# msp430fr5994-LQFP_80.net
KiCad netlist of a schematic drawn in EAGLE
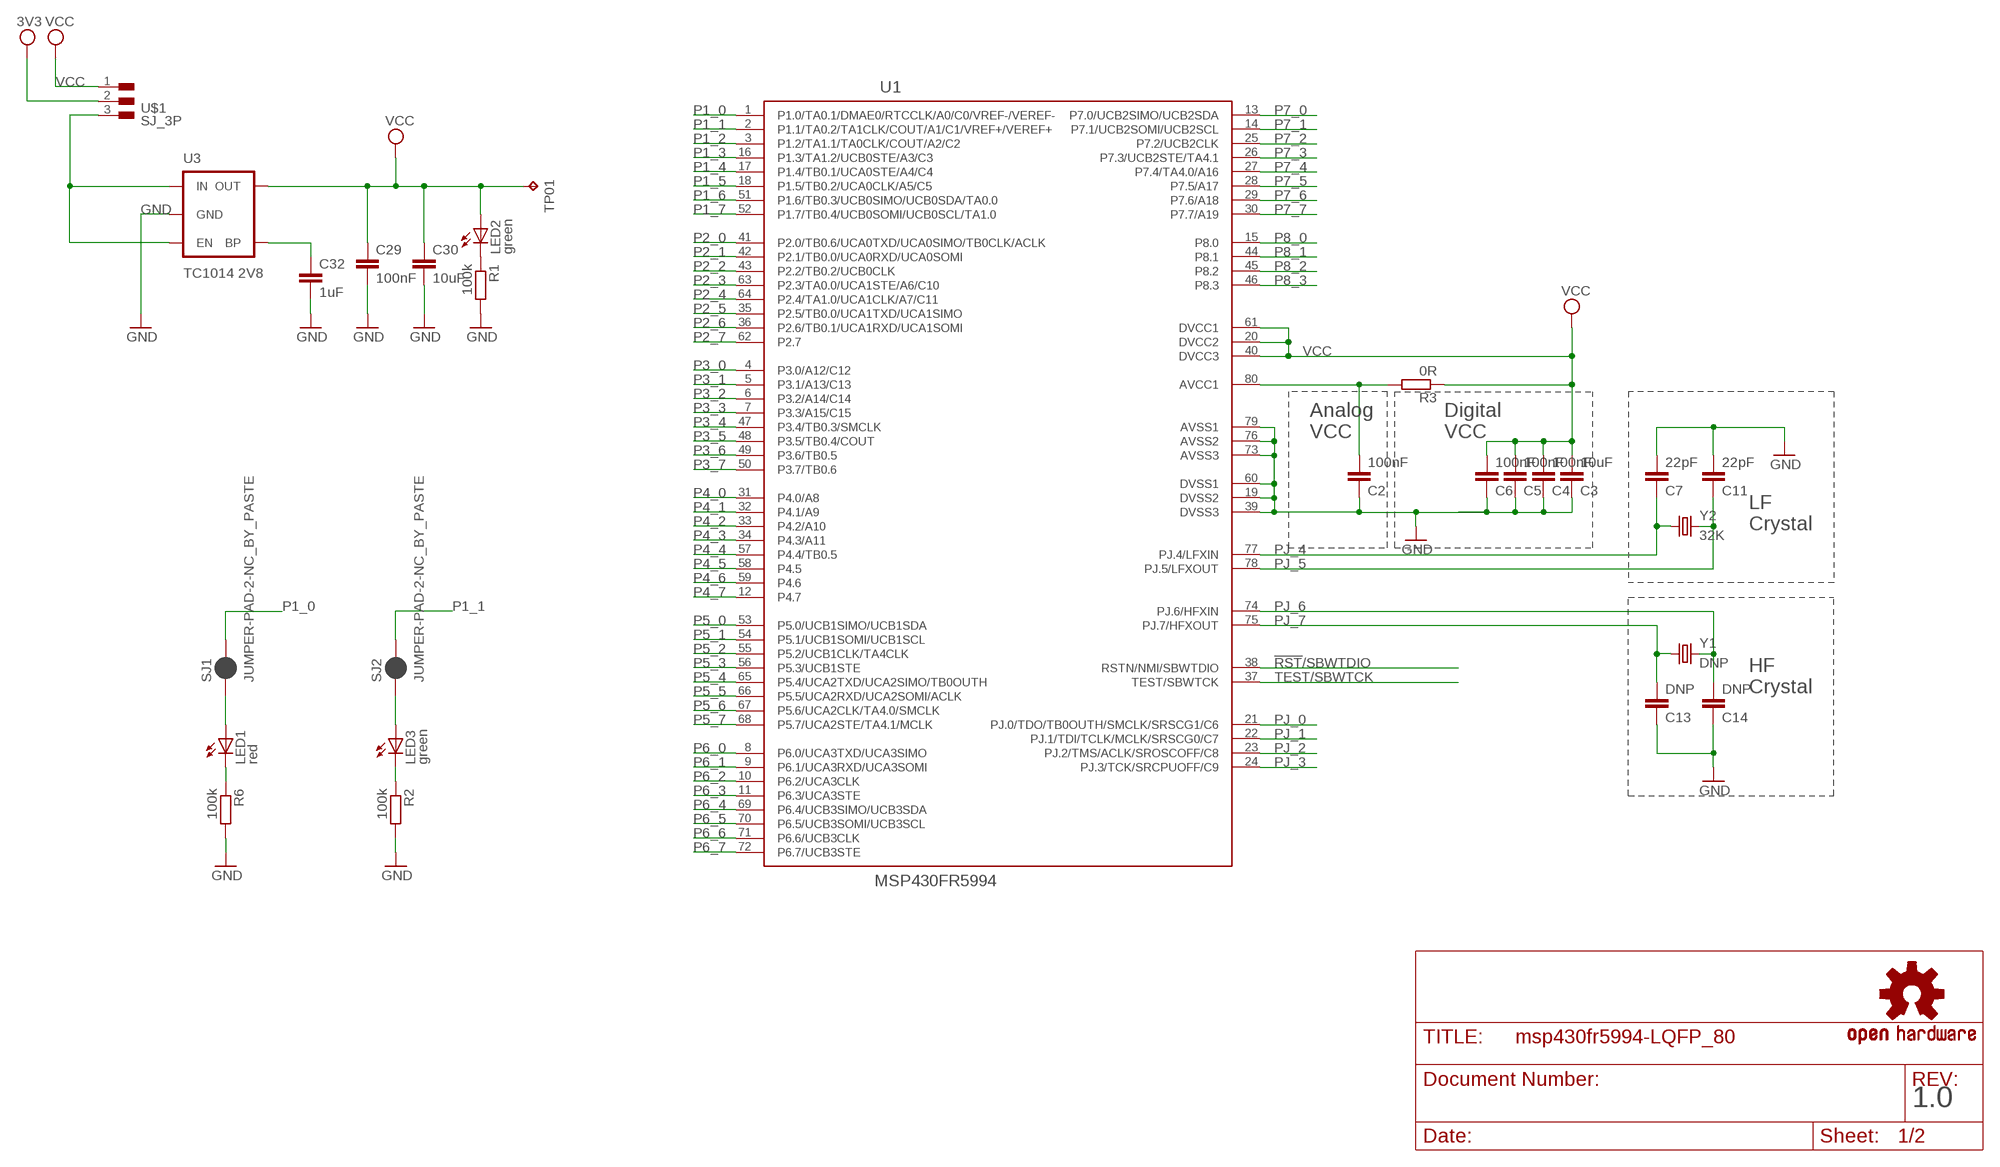
[diagram p0: schematic, sheet 1]
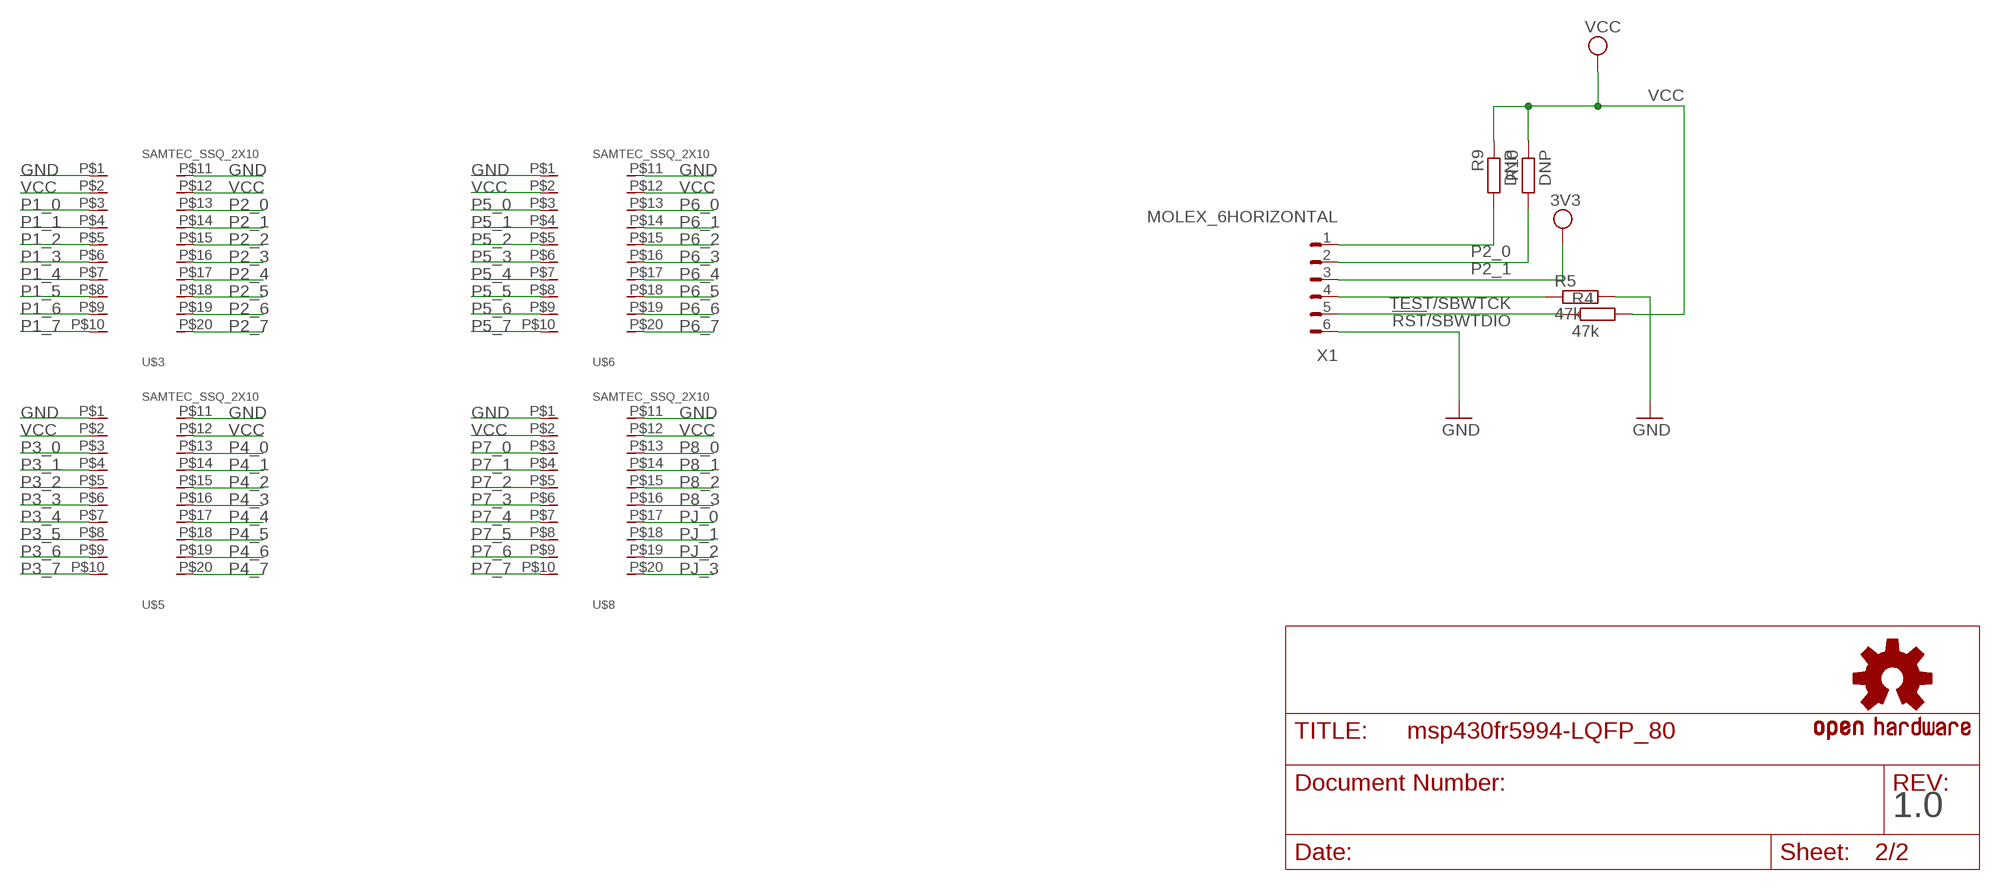
[diagram p1: schematic, sheet 2]

(export (version "E")
  (design (tool "Eeschema 10.0.6"))
  (components
    (comp (ref "R4")
      (value "47k")
      (footprint "eagle-import:R0805W")
      (libsource (lib "eagle-import") (part "R-EU_R0805W"))
    )
    (comp (ref "R5")
      (value "47k")
      (footprint "eagle-import:R0805W")
      (libsource (lib "eagle-import") (part "R-EU_R0805W"))
    )
    (comp (ref "R9")
      (value "DNP")
      (footprint "eagle-import:R0805W")
      (libsource (lib "eagle-import") (part "R-EU_R0805W"))
    )
    (comp (ref "R10")
      (value "DNP")
      (footprint "eagle-import:R0805W")
      (libsource (lib "eagle-import") (part "R-EU_R0805W"))
    )
    (comp (ref "U$2")
      (value "OSHW-LOGOM")
      (footprint "eagle-import:OSHW-LOGO-M")
      (libsource (lib "eagle-import") (part "OSHW-LOGOM"))
    )
    (comp (ref "U$3")
      (value "SAMTEC_SSQ_2X10")
      (footprint "eagle-import:SSQ-110-03-G-D")
      (libsource (lib "eagle-import") (part "SAMTEC_SSQ_2X10"))
    )
    (comp (ref "U$5")
      (value "SAMTEC_SSQ_2X10")
      (footprint "eagle-import:SSQ-110-03-G-D")
      (libsource (lib "eagle-import") (part "SAMTEC_SSQ_2X10"))
    )
    (comp (ref "U$6")
      (value "SAMTEC_SSQ_2X10")
      (footprint "eagle-import:SSQ-110-03-G-D")
      (libsource (lib "eagle-import") (part "SAMTEC_SSQ_2X10"))
    )
    (comp (ref "U$8")
      (value "SAMTEC_SSQ_2X10")
      (footprint "eagle-import:SSQ-110-03-G-D")
      (libsource (lib "eagle-import") (part "SAMTEC_SSQ_2X10"))
    )
    (comp (ref "X1")
      (value "MOLEX_6HORIZONTAL")
      (footprint "eagle-import:0530480610")
      (libsource (lib "eagle-import") (part "MOLEX_6HORIZONTAL"))
    )
    (comp (ref "C2")
      (value "100nF")
      (footprint "eagle-import:C0805")
      (libsource (lib "eagle-import") (part "C-EUC0805"))
    )
    (comp (ref "C3")
      (value "10uF")
      (footprint "eagle-import:C0805")
      (libsource (lib "eagle-import") (part "C-EUC0805"))
    )
    (comp (ref "C4")
      (value "100nF")
      (footprint "eagle-import:C0805")
      (libsource (lib "eagle-import") (part "C-EUC0805"))
    )
    (comp (ref "C5")
      (value "100nF")
      (footprint "eagle-import:C0805")
      (libsource (lib "eagle-import") (part "C-EUC0805"))
    )
    (comp (ref "C6")
      (value "100nF")
      (footprint "eagle-import:C0805")
      (libsource (lib "eagle-import") (part "C-EUC0805"))
    )
    (comp (ref "C7")
      (value "22pF")
      (footprint "eagle-import:C0805")
      (libsource (lib "eagle-import") (part "C-EUC0805"))
    )
    (comp (ref "C11")
      (value "22pF")
      (footprint "eagle-import:C0805")
      (libsource (lib "eagle-import") (part "C-EUC0805"))
    )
    (comp (ref "C13")
      (value "DNP")
      (footprint "eagle-import:C0805")
      (libsource (lib "eagle-import") (part "C-EUC0805"))
    )
    (comp (ref "C14")
      (value "DNP")
      (footprint "eagle-import:C0805")
      (libsource (lib "eagle-import") (part "C-EUC0805"))
    )
    (comp (ref "C29")
      (value "100nF")
      (footprint "eagle-import:C0805")
      (libsource (lib "eagle-import") (part "C-EUC0805"))
    )
    (comp (ref "C30")
      (value "10uF")
      (footprint "eagle-import:C1206")
      (libsource (lib "eagle-import") (part "C-EUC1206"))
    )
    (comp (ref "C32")
      (value "1uF")
      (footprint "eagle-import:C0805")
      (libsource (lib "eagle-import") (part "C-EUC0805"))
    )
    (comp (ref "LED1")
      (value "red")
      (footprint "eagle-import:CHIPLED_0805")
      (libsource (lib "eagle-import") (part "LEDCHIPLED_0805"))
    )
    (comp (ref "LED2")
      (value "green")
      (footprint "eagle-import:CHIPLED_0805")
      (libsource (lib "eagle-import") (part "LEDCHIPLED_0805"))
    )
    (comp (ref "LED3")
      (value "green")
      (footprint "eagle-import:CHIPLED_0805")
      (libsource (lib "eagle-import") (part "LEDCHIPLED_0805"))
    )
    (comp (ref "R1")
      (value "100k")
      (footprint "eagle-import:R0805W")
      (libsource (lib "eagle-import") (part "R-EU_R0805W"))
    )
    (comp (ref "R2")
      (value "100k")
      (footprint "eagle-import:R0805W")
      (libsource (lib "eagle-import") (part "R-EU_R0805W"))
    )
    (comp (ref "R3")
      (value "0R")
      (footprint "eagle-import:R0805W")
      (libsource (lib "eagle-import") (part "R-EU_R0805W"))
    )
    (comp (ref "R6")
      (value "100k")
      (footprint "eagle-import:R0805W")
      (libsource (lib "eagle-import") (part "R-EU_R0805W"))
    )
    (comp (ref "SJ1")
      (value "JUMPER-PAD-2-NC_BY_PASTE")
      (footprint "eagle-import:PAD-JUMPER-2-NC_BY_PASTE_YES_SILK")
      (libsource (lib "eagle-import") (part "JUMPER-PAD-2-NC_BY_PASTE"))
    )
    (comp (ref "SJ2")
      (value "JUMPER-PAD-2-NC_BY_PASTE")
      (footprint "eagle-import:PAD-JUMPER-2-NC_BY_PASTE_YES_SILK")
      (libsource (lib "eagle-import") (part "JUMPER-PAD-2-NC_BY_PASTE"))
    )
    (comp (ref "TP01")
      (value "TPTP12R")
      (footprint "eagle-import:TP12R")
      (libsource (lib "eagle-import") (part "TPTP12R"))
    )
    (comp (ref "U$1")
      (value "SJ_3P")
      (footprint "eagle-import:SJ_3P")
      (libsource (lib "eagle-import") (part "SJ_3P"))
    )
    (comp (ref "U$7")
      (value "OSHW-LOGOM")
      (footprint "eagle-import:OSHW-LOGO-M")
      (libsource (lib "eagle-import") (part "OSHW-LOGOM"))
    )
    (comp (ref "U1")
      (value "MSP430FR5994")
      (footprint "eagle-import:PN80")
      (libsource (lib "eagle-import") (part "MSP430FR5994"))
    )
    (comp (ref "U3")
      (value "TC1014 2V8")
      (footprint "eagle-import:SOT23-5")
      (libsource (lib "eagle-import") (part "V_REG_LDOSMD"))
    )
    (comp (ref "Y1")
      (value "DNP")
      (footprint "eagle-import:CRYSTAL-SMD-11.4X4.35")
      (libsource (lib "eagle-import") (part "CRYSTAL"))
    )
    (comp (ref "Y2")
      (value "32K")
      (footprint "eagle-import:CRYSTAL-SMD-3.2X1.5")
      (libsource (lib "eagle-import") (part "CRYSTAL3.2X1.5"))
    )
  )
  (nets
    (net (code "1") (name "3V3") (class "Default")
      (node (ref "U$1") (pin "2") (pinfunction "2_2") (pintype "passive"))
      (node (ref "X1") (pin "3") (pinfunction "4_3") (pintype "passive"))
    )
    (net (code "2") (name "GND") (class "Default")
      (node (ref "C11") (pin "2") (pinfunction "2_2") (pintype "passive"))
      (node (ref "C13") (pin "1") (pinfunction "1_1") (pintype "passive"))
      (node (ref "C14") (pin "1") (pinfunction "1_1") (pintype "passive"))
      (node (ref "C2") (pin "1") (pinfunction "1_1") (pintype "passive"))
      (node (ref "C29") (pin "2") (pinfunction "2_2") (pintype "passive"))
      (node (ref "C3") (pin "1") (pinfunction "1_1") (pintype "passive"))
      (node (ref "C30") (pin "2") (pinfunction "2_2") (pintype "passive"))
      (node (ref "C32") (pin "2") (pinfunction "2_2") (pintype "passive"))
      (node (ref "C4") (pin "1") (pinfunction "1_1") (pintype "passive"))
      (node (ref "C5") (pin "1") (pinfunction "1_1") (pintype "passive"))
      (node (ref "C6") (pin "1") (pinfunction "1_1") (pintype "passive"))
      (node (ref "C7") (pin "2") (pinfunction "2_2") (pintype "passive"))
      (node (ref "R1") (pin "2") (pinfunction "2_2") (pintype "passive"))
      (node (ref "R2") (pin "2") (pinfunction "2_2") (pintype "passive"))
      (node (ref "R5") (pin "2") (pinfunction "2_2") (pintype "passive"))
      (node (ref "R6") (pin "2") (pinfunction "2_2") (pintype "passive"))
      (node (ref "U$3") (pin "P$1") (pinfunction "P$1_P$1") (pintype "bidirectional"))
      (node (ref "U$3") (pin "P$11") (pinfunction "P$11_P$11") (pintype "bidirectional"))
      (node (ref "U$5") (pin "P$1") (pinfunction "P$1_P$1") (pintype "bidirectional"))
      (node (ref "U$5") (pin "P$11") (pinfunction "P$11_P$11") (pintype "bidirectional"))
      (node (ref "U$6") (pin "P$1") (pinfunction "P$1_P$1") (pintype "bidirectional"))
      (node (ref "U$6") (pin "P$11") (pinfunction "P$11_P$11") (pintype "bidirectional"))
      (node (ref "U$8") (pin "P$1") (pinfunction "P$1_P$1") (pintype "bidirectional"))
      (node (ref "U$8") (pin "P$11") (pinfunction "P$11_P$11") (pintype "bidirectional"))
      (node (ref "U1") (pin "19") (pinfunction "DVSS2_19") (pintype "power_in"))
      (node (ref "U1") (pin "39") (pinfunction "DVSS3_39") (pintype "power_in"))
      (node (ref "U1") (pin "60") (pinfunction "DVSS1_60") (pintype "power_in"))
      (node (ref "U1") (pin "73") (pinfunction "AVSS3_73") (pintype "power_in"))
      (node (ref "U1") (pin "76") (pinfunction "AVSS2_76") (pintype "power_in"))
      (node (ref "U1") (pin "79") (pinfunction "AVSS1_79") (pintype "power_in"))
      (node (ref "U3") (pin "2") (pinfunction "GND_2") (pintype "input"))
      (node (ref "X1") (pin "6") (pinfunction "1_6") (pintype "passive"))
    )
    (net (code "3") (name "Net-(LED1-PadA)") (class "Default")
      (node (ref "LED1") (pin "A") (pinfunction "A_A") (pintype "passive"))
      (node (ref "SJ1") (pin "1") (pinfunction "1_1") (pintype "passive"))
    )
    (net (code "4") (name "Net-(LED1-PadC)") (class "Default")
      (node (ref "LED1") (pin "C") (pinfunction "C_C") (pintype "passive"))
      (node (ref "R6") (pin "1") (pinfunction "1_1") (pintype "passive"))
    )
    (net (code "5") (name "Net-(LED2-PadC)") (class "Default")
      (node (ref "LED2") (pin "C") (pinfunction "C_C") (pintype "passive"))
      (node (ref "R1") (pin "1") (pinfunction "1_1") (pintype "passive"))
    )
    (net (code "6") (name "Net-(LED3-PadA)") (class "Default")
      (node (ref "LED3") (pin "A") (pinfunction "A_A") (pintype "passive"))
      (node (ref "SJ2") (pin "1") (pinfunction "1_1") (pintype "passive"))
    )
    (net (code "7") (name "Net-(LED3-PadC)") (class "Default")
      (node (ref "LED3") (pin "C") (pinfunction "C_C") (pintype "passive"))
      (node (ref "R2") (pin "1") (pinfunction "1_1") (pintype "passive"))
    )
    (net (code "8") (name "Net-(U1-AVCC1)") (class "Default")
      (node (ref "C2") (pin "2") (pinfunction "2_2") (pintype "passive"))
      (node (ref "R3") (pin "2") (pinfunction "2_2") (pintype "passive"))
      (node (ref "U1") (pin "80") (pinfunction "AVCC1_80") (pintype "power_in"))
    )
    (net (code "9") (name "Net-(U3-BP)") (class "Default")
      (node (ref "C32") (pin "1") (pinfunction "1_1") (pintype "passive"))
      (node (ref "U3") (pin "4") (pinfunction "BP_4") (pintype "input"))
    )
    (net (code "10") (name "Net-(U3-EN)") (class "Default")
      (node (ref "U$1") (pin "3") (pinfunction "3_3") (pintype "passive"))
      (node (ref "U3") (pin "1") (pinfunction "IN_1") (pintype "input"))
      (node (ref "U3") (pin "3") (pinfunction "EN_3") (pintype "input"))
    )
    (net (code "11") (name "P1_0") (class "Default")
      (node (ref "SJ1") (pin "2") (pinfunction "2_2") (pintype "passive"))
      (node (ref "U$3") (pin "P$3") (pinfunction "P$3_P$3") (pintype "bidirectional"))
      (node (ref "U1") (pin "1") (pinfunction "P1.0/TA0.1/DMAE0/RTCCLK/A0/C0/VREF-/VEREF-_1") (pintype "power_in"))
    )
    (net (code "12") (name "P1_1") (class "Default")
      (node (ref "SJ2") (pin "2") (pinfunction "2_2") (pintype "passive"))
      (node (ref "U$3") (pin "P$4") (pinfunction "P$4_P$4") (pintype "bidirectional"))
      (node (ref "U1") (pin "2") (pinfunction "P1.1/TA0.2/TA1CLK/COUT/A1/C1/VREF+/VEREF+_2") (pintype "power_in"))
    )
    (net (code "13") (name "P1_2") (class "Default")
      (node (ref "U$3") (pin "P$5") (pinfunction "P$5_P$5") (pintype "bidirectional"))
      (node (ref "U1") (pin "3") (pinfunction "P1.2/TA1.1/TA0CLK/COUT/A2/C2_3") (pintype "power_in"))
    )
    (net (code "14") (name "P1_3") (class "Default")
      (node (ref "U$3") (pin "P$6") (pinfunction "P$6_P$6") (pintype "bidirectional"))
      (node (ref "U1") (pin "16") (pinfunction "P1.3/TA1.2/UCB0STE/A3/C3_16") (pintype "power_in"))
    )
    (net (code "15") (name "P1_4") (class "Default")
      (node (ref "U$3") (pin "P$7") (pinfunction "P$7_P$7") (pintype "bidirectional"))
      (node (ref "U1") (pin "17") (pinfunction "P1.4/TB0.1/UCA0STE/A4/C4_17") (pintype "power_in"))
    )
    (net (code "16") (name "P1_5") (class "Default")
      (node (ref "U$3") (pin "P$8") (pinfunction "P$8_P$8") (pintype "bidirectional"))
      (node (ref "U1") (pin "18") (pinfunction "P1.5/TB0.2/UCA0CLK/A5/C5_18") (pintype "power_in"))
    )
    (net (code "17") (name "P1_6") (class "Default")
      (node (ref "U$3") (pin "P$9") (pinfunction "P$9_P$9") (pintype "bidirectional"))
      (node (ref "U1") (pin "51") (pinfunction "P1.6/TB0.3/UCB0SIMO/UCB0SDA/TA0.0_51") (pintype "power_in"))
    )
    (net (code "18") (name "P1_7") (class "Default")
      (node (ref "U$3") (pin "P$10") (pinfunction "P$10_P$10") (pintype "bidirectional"))
      (node (ref "U1") (pin "52") (pinfunction "P1.7/TB0.4/UCB0SOMI/UCB0SCL/TA1.0_52") (pintype "power_in"))
    )
    (net (code "19") (name "P2_0") (class "Default")
      (node (ref "R9") (pin "2") (pinfunction "2_2") (pintype "passive"))
      (node (ref "U$3") (pin "P$13") (pinfunction "P$13_P$13") (pintype "bidirectional"))
      (node (ref "U1") (pin "41") (pinfunction "P2.0/TB0.6/UCA0TXD/UCA0SIMO/TB0CLK/ACLK_41") (pintype "power_in"))
      (node (ref "X1") (pin "1") (pinfunction "6_1") (pintype "passive"))
    )
    (net (code "20") (name "P2_1") (class "Default")
      (node (ref "R10") (pin "2") (pinfunction "2_2") (pintype "passive"))
      (node (ref "U$3") (pin "P$14") (pinfunction "P$14_P$14") (pintype "bidirectional"))
      (node (ref "U1") (pin "42") (pinfunction "P2.1/TB0.0/UCA0RXD/UCA0SOMI_42") (pintype "power_in"))
      (node (ref "X1") (pin "2") (pinfunction "5_2") (pintype "passive"))
    )
    (net (code "21") (name "P2_2") (class "Default")
      (node (ref "U$3") (pin "P$15") (pinfunction "P$15_P$15") (pintype "bidirectional"))
      (node (ref "U1") (pin "43") (pinfunction "P2.2/TB0.2/UCB0CLK_43") (pintype "power_in"))
    )
    (net (code "22") (name "P2_3") (class "Default")
      (node (ref "U$3") (pin "P$16") (pinfunction "P$16_P$16") (pintype "bidirectional"))
      (node (ref "U1") (pin "63") (pinfunction "P2.3/TA0.0/UCA1STE/A6/C10_63") (pintype "power_in"))
    )
    (net (code "23") (name "P2_4") (class "Default")
      (node (ref "U$3") (pin "P$17") (pinfunction "P$17_P$17") (pintype "bidirectional"))
      (node (ref "U1") (pin "64") (pinfunction "P2.4/TA1.0/UCA1CLK/A7/C11_64") (pintype "power_in"))
    )
    (net (code "24") (name "P2_5") (class "Default")
      (node (ref "U$3") (pin "P$18") (pinfunction "P$18_P$18") (pintype "bidirectional"))
      (node (ref "U1") (pin "35") (pinfunction "P2.5/TB0.0/UCA1TXD/UCA1SIMO_35") (pintype "power_in"))
    )
    (net (code "25") (name "P2_6") (class "Default")
      (node (ref "U$3") (pin "P$19") (pinfunction "P$19_P$19") (pintype "bidirectional"))
      (node (ref "U1") (pin "36") (pinfunction "P2.6/TB0.1/UCA1RXD/UCA1SOMI_36") (pintype "power_in"))
    )
    (net (code "26") (name "P2_7") (class "Default")
      (node (ref "U$3") (pin "P$20") (pinfunction "P$20_P$20") (pintype "bidirectional"))
      (node (ref "U1") (pin "62") (pinfunction "P2.7_62") (pintype "power_in"))
    )
    (net (code "27") (name "P3_0") (class "Default")
      (node (ref "U$5") (pin "P$3") (pinfunction "P$3_P$3") (pintype "bidirectional"))
      (node (ref "U1") (pin "4") (pinfunction "P3.0/A12/C12_4") (pintype "power_in"))
    )
    (net (code "28") (name "P3_1") (class "Default")
      (node (ref "U$5") (pin "P$4") (pinfunction "P$4_P$4") (pintype "bidirectional"))
      (node (ref "U1") (pin "5") (pinfunction "P3.1/A13/C13_5") (pintype "power_in"))
    )
    (net (code "29") (name "P3_2") (class "Default")
      (node (ref "U$5") (pin "P$5") (pinfunction "P$5_P$5") (pintype "bidirectional"))
      (node (ref "U1") (pin "6") (pinfunction "P3.2/A14/C14_6") (pintype "power_in"))
    )
    (net (code "30") (name "P3_3") (class "Default")
      (node (ref "U$5") (pin "P$6") (pinfunction "P$6_P$6") (pintype "bidirectional"))
      (node (ref "U1") (pin "7") (pinfunction "P3.3/A15/C15_7") (pintype "power_in"))
    )
    (net (code "31") (name "P3_4") (class "Default")
      (node (ref "U$5") (pin "P$7") (pinfunction "P$7_P$7") (pintype "bidirectional"))
      (node (ref "U1") (pin "47") (pinfunction "P3.4/TB0.3/SMCLK_47") (pintype "power_in"))
    )
    (net (code "32") (name "P3_5") (class "Default")
      (node (ref "U$5") (pin "P$8") (pinfunction "P$8_P$8") (pintype "bidirectional"))
      (node (ref "U1") (pin "48") (pinfunction "P3.5/TB0.4/COUT_48") (pintype "power_in"))
    )
    (net (code "33") (name "P3_6") (class "Default")
      (node (ref "U$5") (pin "P$9") (pinfunction "P$9_P$9") (pintype "bidirectional"))
      (node (ref "U1") (pin "49") (pinfunction "P3.6/TB0.5_49") (pintype "power_in"))
    )
    (net (code "34") (name "P3_7") (class "Default")
      (node (ref "U$5") (pin "P$10") (pinfunction "P$10_P$10") (pintype "bidirectional"))
      (node (ref "U1") (pin "50") (pinfunction "P3.7/TB0.6_50") (pintype "power_in"))
    )
    (net (code "35") (name "P4_0") (class "Default")
      (node (ref "U$5") (pin "P$13") (pinfunction "P$13_P$13") (pintype "bidirectional"))
      (node (ref "U1") (pin "31") (pinfunction "P4.0/A8_31") (pintype "power_in"))
    )
    (net (code "36") (name "P4_1") (class "Default")
      (node (ref "U$5") (pin "P$14") (pinfunction "P$14_P$14") (pintype "bidirectional"))
      (node (ref "U1") (pin "32") (pinfunction "P4.1/A9_32") (pintype "power_in"))
    )
    (net (code "37") (name "P4_2") (class "Default")
      (node (ref "U$5") (pin "P$15") (pinfunction "P$15_P$15") (pintype "bidirectional"))
      (node (ref "U1") (pin "33") (pinfunction "P4.2/A10_33") (pintype "power_in"))
    )
    (net (code "38") (name "P4_3") (class "Default")
      (node (ref "U$5") (pin "P$16") (pinfunction "P$16_P$16") (pintype "bidirectional"))
      (node (ref "U1") (pin "34") (pinfunction "P4.3/A11_34") (pintype "power_in"))
    )
    (net (code "39") (name "P4_4") (class "Default")
      (node (ref "U$5") (pin "P$17") (pinfunction "P$17_P$17") (pintype "bidirectional"))
      (node (ref "U1") (pin "57") (pinfunction "P4.4/TB0.5_57") (pintype "power_in"))
    )
    (net (code "40") (name "P4_5") (class "Default")
      (node (ref "U$5") (pin "P$18") (pinfunction "P$18_P$18") (pintype "bidirectional"))
      (node (ref "U1") (pin "58") (pinfunction "P4.5_58") (pintype "power_in"))
    )
    (net (code "41") (name "P4_6") (class "Default")
      (node (ref "U$5") (pin "P$19") (pinfunction "P$19_P$19") (pintype "bidirectional"))
      (node (ref "U1") (pin "59") (pinfunction "P4.6_59") (pintype "power_in"))
    )
    (net (code "42") (name "P4_7") (class "Default")
      (node (ref "U$5") (pin "P$20") (pinfunction "P$20_P$20") (pintype "bidirectional"))
      (node (ref "U1") (pin "12") (pinfunction "P4.7_12") (pintype "power_in"))
    )
    (net (code "43") (name "P5_0") (class "Default")
      (node (ref "U$6") (pin "P$3") (pinfunction "P$3_P$3") (pintype "bidirectional"))
      (node (ref "U1") (pin "53") (pinfunction "P5.0/UCB1SIMO/UCB1SDA_53") (pintype "power_in"))
    )
    (net (code "44") (name "P5_1") (class "Default")
      (node (ref "U$6") (pin "P$4") (pinfunction "P$4_P$4") (pintype "bidirectional"))
      (node (ref "U1") (pin "54") (pinfunction "P5.1/UCB1SOMI/UCB1SCL_54") (pintype "power_in"))
    )
    (net (code "45") (name "P5_2") (class "Default")
      (node (ref "U$6") (pin "P$5") (pinfunction "P$5_P$5") (pintype "bidirectional"))
      (node (ref "U1") (pin "55") (pinfunction "P5.2/UCB1CLK/TA4CLK_55") (pintype "power_in"))
    )
    (net (code "46") (name "P5_3") (class "Default")
      (node (ref "U$6") (pin "P$6") (pinfunction "P$6_P$6") (pintype "bidirectional"))
      (node (ref "U1") (pin "56") (pinfunction "P5.3/UCB1STE_56") (pintype "power_in"))
    )
    (net (code "47") (name "P5_4") (class "Default")
      (node (ref "U$6") (pin "P$7") (pinfunction "P$7_P$7") (pintype "bidirectional"))
      (node (ref "U1") (pin "65") (pinfunction "P5.4/UCA2TXD/UCA2SIMO/TB0OUTH_65") (pintype "power_in"))
    )
    (net (code "48") (name "P5_5") (class "Default")
      (node (ref "U$6") (pin "P$8") (pinfunction "P$8_P$8") (pintype "bidirectional"))
      (node (ref "U1") (pin "66") (pinfunction "P5.5/UCA2RXD/UCA2SOMI/ACLK_66") (pintype "power_in"))
    )
    (net (code "49") (name "P5_6") (class "Default")
      (node (ref "U$6") (pin "P$9") (pinfunction "P$9_P$9") (pintype "bidirectional"))
      (node (ref "U1") (pin "67") (pinfunction "P5.6/UCA2CLK/TA4.0/SMCLK_67") (pintype "power_in"))
    )
    (net (code "50") (name "P5_7") (class "Default")
      (node (ref "U$6") (pin "P$10") (pinfunction "P$10_P$10") (pintype "bidirectional"))
      (node (ref "U1") (pin "68") (pinfunction "P5.7/UCA2STE/TA4.1/MCLK_68") (pintype "power_in"))
    )
    (net (code "51") (name "P6_0") (class "Default")
      (node (ref "U$6") (pin "P$13") (pinfunction "P$13_P$13") (pintype "bidirectional"))
      (node (ref "U1") (pin "8") (pinfunction "P6.0/UCA3TXD/UCA3SIMO_8") (pintype "power_in"))
    )
    (net (code "52") (name "P6_1") (class "Default")
      (node (ref "U$6") (pin "P$14") (pinfunction "P$14_P$14") (pintype "bidirectional"))
      (node (ref "U1") (pin "9") (pinfunction "P6.1/UCA3RXD/UCA3SOMI_9") (pintype "power_in"))
    )
    (net (code "53") (name "P6_2") (class "Default")
      (node (ref "U$6") (pin "P$15") (pinfunction "P$15_P$15") (pintype "bidirectional"))
      (node (ref "U1") (pin "10") (pinfunction "P6.2/UCA3CLK_10") (pintype "power_in"))
    )
    (net (code "54") (name "P6_3") (class "Default")
      (node (ref "U$6") (pin "P$16") (pinfunction "P$16_P$16") (pintype "bidirectional"))
      (node (ref "U1") (pin "11") (pinfunction "P6.3/UCA3STE_11") (pintype "power_in"))
    )
    (net (code "55") (name "P6_4") (class "Default")
      (node (ref "U$6") (pin "P$17") (pinfunction "P$17_P$17") (pintype "bidirectional"))
      (node (ref "U1") (pin "69") (pinfunction "P6.4/UCB3SIMO/UCB3SDA_69") (pintype "power_in"))
    )
    (net (code "56") (name "P6_5") (class "Default")
      (node (ref "U$6") (pin "P$18") (pinfunction "P$18_P$18") (pintype "bidirectional"))
      (node (ref "U1") (pin "70") (pinfunction "P6.5/UCB3SOMI/UCB3SCL_70") (pintype "power_in"))
    )
    (net (code "57") (name "P6_6") (class "Default")
      (node (ref "U$6") (pin "P$19") (pinfunction "P$19_P$19") (pintype "bidirectional"))
      (node (ref "U1") (pin "71") (pinfunction "P6.6/UCB3CLK_71") (pintype "power_in"))
    )
    (net (code "58") (name "P6_7") (class "Default")
      (node (ref "U$6") (pin "P$20") (pinfunction "P$20_P$20") (pintype "bidirectional"))
      (node (ref "U1") (pin "72") (pinfunction "P6.7/UCB3STE_72") (pintype "power_in"))
    )
    (net (code "59") (name "P7_0") (class "Default")
      (node (ref "U$8") (pin "P$3") (pinfunction "P$3_P$3") (pintype "bidirectional"))
      (node (ref "U1") (pin "13") (pinfunction "P7.0/UCB2SIMO/UCB2SDA_13") (pintype "power_in"))
    )
    (net (code "60") (name "P7_1") (class "Default")
      (node (ref "U$8") (pin "P$4") (pinfunction "P$4_P$4") (pintype "bidirectional"))
      (node (ref "U1") (pin "14") (pinfunction "P7.1/UCB2SOMI/UCB2SCL_14") (pintype "power_in"))
    )
    (net (code "61") (name "P7_2") (class "Default")
      (node (ref "U$8") (pin "P$5") (pinfunction "P$5_P$5") (pintype "bidirectional"))
      (node (ref "U1") (pin "25") (pinfunction "P7.2/UCB2CLK_25") (pintype "power_in"))
    )
    (net (code "62") (name "P7_3") (class "Default")
      (node (ref "U$8") (pin "P$6") (pinfunction "P$6_P$6") (pintype "bidirectional"))
      (node (ref "U1") (pin "26") (pinfunction "P7.3/UCB2STE/TA4.1_26") (pintype "power_in"))
    )
    (net (code "63") (name "P7_4") (class "Default")
      (node (ref "U$8") (pin "P$7") (pinfunction "P$7_P$7") (pintype "bidirectional"))
      (node (ref "U1") (pin "27") (pinfunction "P7.4/TA4.0/A16_27") (pintype "power_in"))
    )
    (net (code "64") (name "P7_5") (class "Default")
      (node (ref "U$8") (pin "P$8") (pinfunction "P$8_P$8") (pintype "bidirectional"))
      (node (ref "U1") (pin "28") (pinfunction "P7.5/A17_28") (pintype "power_in"))
    )
    (net (code "65") (name "P7_6") (class "Default")
      (node (ref "U$8") (pin "P$9") (pinfunction "P$9_P$9") (pintype "bidirectional"))
      (node (ref "U1") (pin "29") (pinfunction "P7.6/A18_29") (pintype "power_in"))
    )
    (net (code "66") (name "P7_7") (class "Default")
      (node (ref "U$8") (pin "P$10") (pinfunction "P$10_P$10") (pintype "bidirectional"))
      (node (ref "U1") (pin "30") (pinfunction "P7.7/A19_30") (pintype "power_in"))
    )
    (net (code "67") (name "P8_0") (class "Default")
      (node (ref "U$8") (pin "P$13") (pinfunction "P$13_P$13") (pintype "bidirectional"))
      (node (ref "U1") (pin "15") (pinfunction "P8.0_15") (pintype "power_in"))
    )
    (net (code "68") (name "P8_1") (class "Default")
      (node (ref "U$8") (pin "P$14") (pinfunction "P$14_P$14") (pintype "bidirectional"))
      (node (ref "U1") (pin "44") (pinfunction "P8.1_44") (pintype "power_in"))
    )
    (net (code "69") (name "P8_2") (class "Default")
      (node (ref "U$8") (pin "P$15") (pinfunction "P$15_P$15") (pintype "bidirectional"))
      (node (ref "U1") (pin "45") (pinfunction "P8.2_45") (pintype "power_in"))
    )
    (net (code "70") (name "P8_3") (class "Default")
      (node (ref "U$8") (pin "P$16") (pinfunction "P$16_P$16") (pintype "bidirectional"))
      (node (ref "U1") (pin "46") (pinfunction "P8.3_46") (pintype "power_in"))
    )
    (net (code "71") (name "PJ_0") (class "Default")
      (node (ref "U$8") (pin "P$17") (pinfunction "P$17_P$17") (pintype "bidirectional"))
      (node (ref "U1") (pin "21") (pinfunction "PJ.0/TDO/TB0OUTH/SMCLK/SRSCG1/C6_21") (pintype "power_in"))
    )
    (net (code "72") (name "PJ_1") (class "Default")
      (node (ref "U$8") (pin "P$18") (pinfunction "P$18_P$18") (pintype "bidirectional"))
      (node (ref "U1") (pin "22") (pinfunction "PJ.1/TDI/TCLK/MCLK/SRSCG0/C7_22") (pintype "power_in"))
    )
    (net (code "73") (name "PJ_2") (class "Default")
      (node (ref "U$8") (pin "P$19") (pinfunction "P$19_P$19") (pintype "bidirectional"))
      (node (ref "U1") (pin "23") (pinfunction "PJ.2/TMS/ACLK/SROSCOFF/C8_23") (pintype "power_in"))
    )
    (net (code "74") (name "PJ_3") (class "Default")
      (node (ref "U$8") (pin "P$20") (pinfunction "P$20_P$20") (pintype "bidirectional"))
      (node (ref "U1") (pin "24") (pinfunction "PJ.3/TCK/SRCPUOFF/C9_24") (pintype "power_in"))
    )
    (net (code "75") (name "PJ_4") (class "Default")
      (node (ref "C7") (pin "1") (pinfunction "1_1") (pintype "passive"))
      (node (ref "U1") (pin "77") (pinfunction "PJ.4/LFXIN_77") (pintype "power_in"))
      (node (ref "Y2") (pin "P$1") (pinfunction "1_P$1") (pintype "passive"))
    )
    (net (code "76") (name "PJ_5") (class "Default")
      (node (ref "C11") (pin "1") (pinfunction "1_1") (pintype "passive"))
      (node (ref "U1") (pin "78") (pinfunction "PJ.5/LFXOUT_78") (pintype "power_in"))
      (node (ref "Y2") (pin "P$2") (pinfunction "2_P$2") (pintype "passive"))
    )
    (net (code "77") (name "PJ_6") (class "Default")
      (node (ref "C14") (pin "2") (pinfunction "2_2") (pintype "passive"))
      (node (ref "U1") (pin "74") (pinfunction "PJ.6/HFXIN_74") (pintype "power_in"))
      (node (ref "Y1") (pin "2") (pinfunction "2_2") (pintype "passive"))
    )
    (net (code "78") (name "PJ_7") (class "Default")
      (node (ref "C13") (pin "2") (pinfunction "2_2") (pintype "passive"))
      (node (ref "U1") (pin "75") (pinfunction "PJ.7/HFXOUT_75") (pintype "power_in"))
      (node (ref "Y1") (pin "1") (pinfunction "1_1") (pintype "passive"))
    )
    (net (code "79") (name "TEST{slash}SBWTCK") (class "Default")
      (node (ref "R5") (pin "1") (pinfunction "1_1") (pintype "passive"))
      (node (ref "U1") (pin "37") (pinfunction "TEST/SBWTCK_37") (pintype "power_in"))
      (node (ref "X1") (pin "4") (pinfunction "3_4") (pintype "passive"))
    )
    (net (code "80") (name "VCC") (class "Default")
      (node (ref "C29") (pin "1") (pinfunction "1_1") (pintype "passive"))
      (node (ref "C3") (pin "2") (pinfunction "2_2") (pintype "passive"))
      (node (ref "C30") (pin "1") (pinfunction "1_1") (pintype "passive"))
      (node (ref "C4") (pin "2") (pinfunction "2_2") (pintype "passive"))
      (node (ref "C5") (pin "2") (pinfunction "2_2") (pintype "passive"))
      (node (ref "C6") (pin "2") (pinfunction "2_2") (pintype "passive"))
      (node (ref "LED2") (pin "A") (pinfunction "A_A") (pintype "passive"))
      (node (ref "R10") (pin "1") (pinfunction "1_1") (pintype "passive"))
      (node (ref "R3") (pin "1") (pinfunction "1_1") (pintype "passive"))
      (node (ref "R4") (pin "2") (pinfunction "2_2") (pintype "passive"))
      (node (ref "R9") (pin "1") (pinfunction "1_1") (pintype "passive"))
      (node (ref "TP01") (pin "TP") (pinfunction "TP_TP") (pintype "input"))
      (node (ref "U$1") (pin "1") (pinfunction "1_1") (pintype "passive"))
      (node (ref "U$3") (pin "P$12") (pinfunction "P$12_P$12") (pintype "bidirectional"))
      (node (ref "U$3") (pin "P$2") (pinfunction "P$2_P$2") (pintype "bidirectional"))
      (node (ref "U$5") (pin "P$12") (pinfunction "P$12_P$12") (pintype "bidirectional"))
      (node (ref "U$5") (pin "P$2") (pinfunction "P$2_P$2") (pintype "bidirectional"))
      (node (ref "U$6") (pin "P$12") (pinfunction "P$12_P$12") (pintype "bidirectional"))
      (node (ref "U$6") (pin "P$2") (pinfunction "P$2_P$2") (pintype "bidirectional"))
      (node (ref "U$8") (pin "P$12") (pinfunction "P$12_P$12") (pintype "bidirectional"))
      (node (ref "U$8") (pin "P$2") (pinfunction "P$2_P$2") (pintype "bidirectional"))
      (node (ref "U1") (pin "20") (pinfunction "DVCC2_20") (pintype "power_in"))
      (node (ref "U1") (pin "40") (pinfunction "DVCC3_40") (pintype "power_in"))
      (node (ref "U1") (pin "61") (pinfunction "DVCC1_61") (pintype "power_in"))
      (node (ref "U3") (pin "5") (pinfunction "OUT_5") (pintype "passive"))
    )
    (net (code "81") (name "~{RST}{slash}SBWTDIO") (class "Default")
      (node (ref "R4") (pin "1") (pinfunction "1_1") (pintype "passive"))
      (node (ref "U1") (pin "38") (pinfunction "RSTN/NMI/SBWTDIO_38") (pintype "power_in"))
      (node (ref "X1") (pin "5") (pinfunction "2_5") (pintype "passive"))
    )
  )
)
